# Shield.net
KiCad netlist of a schematic drawn in Altium Designer
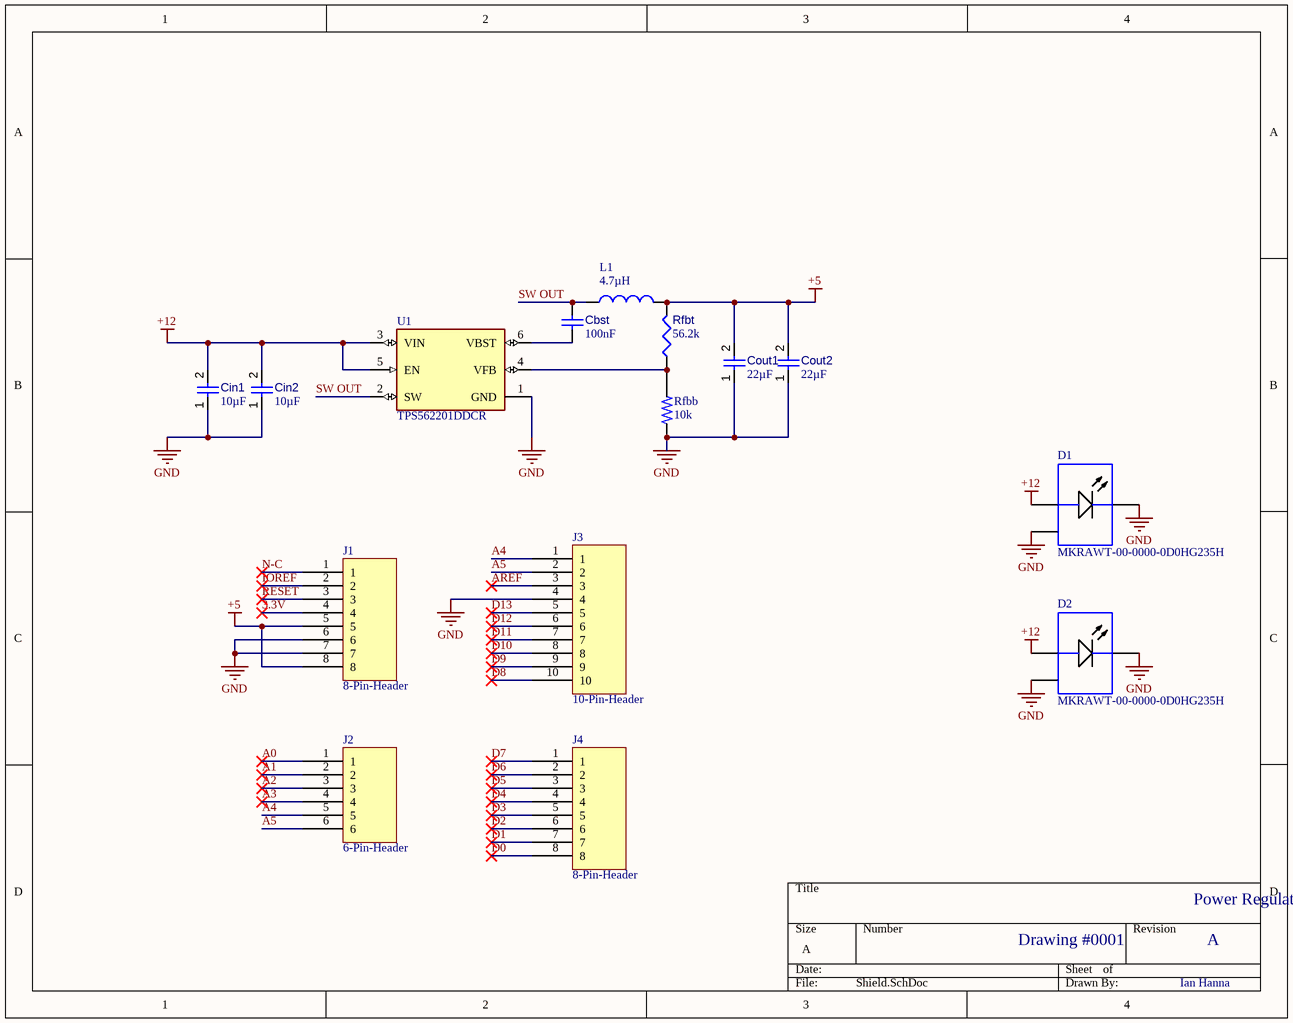
[diagram p0: Shield.SchDoc]

(export (version "E")
  (design (tool "Eeschema 10.0.6"))
  (components
    (comp (ref "Cbst")
      (value "100nF")
      (footprint "C0805")
      (description "0805 100 nF 25V ±10 % Tolerance X7R Surface Mount Multilayer Ceramic Capacitor")
      (fields (field (name "TOLERANCE") "10%") (field (name "Comment") "08053C104KAT2A"))
      (libsource (lib "") (part "CAP-NP-2_1"))
    )
    (comp (ref "Cin1")
      (value "10µF")
      (footprint "C0805")
      (fields (field (name "Comment") "MSAST219LB5106KTNA01"))
      (libsource (lib "Ian Hanna") (part "CAP-NP-2"))
    )
    (comp (ref "Cin2")
      (value "10µF")
      (footprint "C0805")
      (fields (field (name "Comment") "MSAST219LB5106KTNA01"))
      (libsource (lib "Ian Hanna") (part "CAP-NP-2"))
    )
    (comp (ref "Cout1")
      (value "22µF")
      (footprint "C0805")
      (fields (field (name "Comment") "MSASL219LB5226MTNA01"))
      (libsource (lib "Ian Hanna") (part "CAP-NP-2"))
    )
    (comp (ref "Cout2")
      (value "22µF")
      (footprint "C0805")
      (fields (field (name "Comment") "MSASL219LB5226MTNA01"))
      (libsource (lib "Ian Hanna") (part "CAP-NP-2"))
    )
    (comp (ref "D1")
      (value "MKRAWT-00-0000-0D0HG235H")
      (footprint "CREE-MK-R-2_V")
      (description "LED, White, 12 V, 2-Pin SMD, RoHS, Tape and Reel")
      (libsource (lib "Altium Content Vault") (part "LED_WHITE-3"))
    )
    (comp (ref "D2")
      (value "MKRAWT-00-0000-0D0HG235H")
      (footprint "CREE-MK-R-2_V")
      (description "LED, White, 12 V, 2-Pin SMD, RoHS, Tape and Reel")
      (libsource (lib "Altium Content Vault") (part "LED_WHITE-3"))
    )
    (comp (ref "J1")
      (value "8-Pin-Header")
      (footprint "8-Pin-Header-Footprint-1")
      (libsource (lib "Ian Hanna") (part "8-Pin-Header-Symbol-1"))
    )
    (comp (ref "J2")
      (value "6-Pin-Header")
      (footprint "6-Pin-Header-Footprint-1")
      (libsource (lib "Ian Hanna") (part "SSQ-106-03-T-S-Symbol-1"))
    )
    (comp (ref "J3")
      (value "10-Pin-Header")
      (footprint "10-Pin-Header-Footprint-1")
      (libsource (lib "Ian Hanna") (part "SSQ-110-03-T-S-Symbol-1"))
    )
    (comp (ref "J4")
      (value "8-Pin-Header")
      (footprint "8-Pin-Header-Footprint-1")
      (libsource (lib "Ian Hanna") (part "8-Pin-Header-Symbol-1"))
    )
    (comp (ref "L1")
      (value "4.7µH")
      (footprint "SRN6045")
      (description "Inductor Power Semi-Shielded Wirewound 4.7uH 30% 100KHz 15Q-Factor Ferrite 3A 37.6mOhm DCR T/R")
      (fields (field (name "TOLERANCE") "30%") (field (name "Comment") "SRN6045-4R7Y"))
      (libsource (lib "Ian Hanna") (part "IND-2"))
    )
    (comp (ref "Rfbb")
      (value "10k")
      (footprint "RESC0603X26N")
      (description "10 kOhms Â±1% 0.05W, 1/20W Chip Resistor 0201 (0603 Metric) Moisture Resistant Thick Film")
      (fields (field (name "MF") "Yageo") (field (name "MP") "RC0201FR-0710KL"))
      (libsource (lib "Ian Hanna") (part "RC0201FR-0710KL"))
    )
    (comp (ref "Rfbt")
      (value "56.2k")
      (footprint "RESC0603X26N")
      (description "Res Thick Film 0201 56.2K Ohm 1% 0.05W(1/20W) ±200ppm/C Molded SMD Paper T/R")
      (fields (field (name "TOLERANCE") "1%") (field (name "Comment") "RC0201FR-0756K2L"))
      (libsource (lib "Ian Hanna") (part "RES-2"))
    )
    (comp (ref "U1")
      (value "TPS562201DDCR")
      (footprint "FP-DDC0006A-IPC_C")
      (description "IC REG BUCK ADJ 2A TSOT23-6")
      (libsource (lib "Altium Content Vault") (part "957e164956730ea4bf6293280af19fc"))
    )
  )
  (nets
    (net (code "1") (name "+5") (class "Default")
      (node (ref "Cout1") (pin "2") (pinfunction "2_2") (pintype "passive"))
      (node (ref "Cout2") (pin "2") (pinfunction "2_2") (pintype "passive"))
      (node (ref "J1") (pin "5") (pinfunction "5_5") (pintype "passive"))
      (node (ref "J1") (pin "8") (pinfunction "8_8") (pintype "passive"))
      (node (ref "L1") (pin "2") (pinfunction "2_2") (pintype "passive"))
      (node (ref "Rfbt") (pin "2") (pinfunction "2_2") (pintype "passive"))
    )
    (net (code "2") (name "+12") (class "Default")
      (node (ref "Cin1") (pin "2") (pinfunction "2_2") (pintype "passive"))
      (node (ref "Cin2") (pin "2") (pinfunction "2_2") (pintype "passive"))
      (node (ref "D1") (pin "1") (pinfunction "A_1") (pintype "passive"))
      (node (ref "D2") (pin "1") (pinfunction "A_1") (pintype "passive"))
      (node (ref "U1") (pin "3") (pinfunction "VIN_3") (pintype "bidirectional"))
      (node (ref "U1") (pin "5") (pinfunction "EN_5") (pintype "input"))
    )
    (net (code "3") (name "/3.3V") (class "Default")
      (node (ref "J1") (pin "4") (pinfunction "4_4") (pintype "passive+no_connect"))
    )
    (net (code "4") (name "/A0") (class "Default")
      (node (ref "J2") (pin "1") (pinfunction "1_1") (pintype "passive+no_connect"))
    )
    (net (code "5") (name "/A1") (class "Default")
      (node (ref "J2") (pin "2") (pinfunction "2_2") (pintype "passive+no_connect"))
    )
    (net (code "6") (name "/A2") (class "Default")
      (node (ref "J2") (pin "3") (pinfunction "3_3") (pintype "passive+no_connect"))
    )
    (net (code "7") (name "/A3") (class "Default")
      (node (ref "J2") (pin "4") (pinfunction "4_4") (pintype "passive+no_connect"))
    )
    (net (code "8") (name "/A4") (class "Default")
      (node (ref "J2") (pin "5") (pinfunction "5_5") (pintype "passive"))
      (node (ref "J3") (pin "1") (pinfunction "1_1") (pintype "passive"))
    )
    (net (code "9") (name "/A5") (class "Default")
      (node (ref "J2") (pin "6") (pinfunction "6_6") (pintype "passive"))
      (node (ref "J3") (pin "2") (pinfunction "2_2") (pintype "passive"))
    )
    (net (code "10") (name "/AREF") (class "Default")
      (node (ref "J3") (pin "3") (pinfunction "3_3") (pintype "passive+no_connect"))
    )
    (net (code "11") (name "/D0") (class "Default")
      (node (ref "J4") (pin "8") (pinfunction "8_8") (pintype "passive+no_connect"))
    )
    (net (code "12") (name "/D1") (class "Default")
      (node (ref "J4") (pin "7") (pinfunction "7_7") (pintype "passive+no_connect"))
    )
    (net (code "13") (name "/D2") (class "Default")
      (node (ref "J4") (pin "6") (pinfunction "6_6") (pintype "passive+no_connect"))
    )
    (net (code "14") (name "/D3") (class "Default")
      (node (ref "J4") (pin "5") (pinfunction "5_5") (pintype "passive+no_connect"))
    )
    (net (code "15") (name "/D4") (class "Default")
      (node (ref "J4") (pin "4") (pinfunction "4_4") (pintype "passive+no_connect"))
    )
    (net (code "16") (name "/D5") (class "Default")
      (node (ref "J4") (pin "3") (pinfunction "3_3") (pintype "passive+no_connect"))
    )
    (net (code "17") (name "/D6") (class "Default")
      (node (ref "J4") (pin "2") (pinfunction "2_2") (pintype "passive+no_connect"))
    )
    (net (code "18") (name "/D7") (class "Default")
      (node (ref "J4") (pin "1") (pinfunction "1_1") (pintype "passive+no_connect"))
    )
    (net (code "19") (name "/D8") (class "Default")
      (node (ref "J3") (pin "10") (pinfunction "10_10") (pintype "passive+no_connect"))
    )
    (net (code "20") (name "/D9") (class "Default")
      (node (ref "J3") (pin "9") (pinfunction "9_9") (pintype "passive+no_connect"))
    )
    (net (code "21") (name "/D10") (class "Default")
      (node (ref "J3") (pin "8") (pinfunction "8_8") (pintype "passive+no_connect"))
    )
    (net (code "22") (name "/D11") (class "Default")
      (node (ref "J3") (pin "7") (pinfunction "7_7") (pintype "passive+no_connect"))
    )
    (net (code "23") (name "/D12") (class "Default")
      (node (ref "J3") (pin "6") (pinfunction "6_6") (pintype "passive+no_connect"))
    )
    (net (code "24") (name "/D13") (class "Default")
      (node (ref "J3") (pin "5") (pinfunction "5_5") (pintype "passive+no_connect"))
    )
    (net (code "25") (name "/IOREF") (class "Default")
      (node (ref "J1") (pin "2") (pinfunction "2_2") (pintype "passive+no_connect"))
    )
    (net (code "26") (name "/N-C") (class "Default")
      (node (ref "J1") (pin "1") (pinfunction "1_1") (pintype "passive+no_connect"))
    )
    (net (code "27") (name "/RESET") (class "Default")
      (node (ref "J1") (pin "3") (pinfunction "3_3") (pintype "passive+no_connect"))
    )
    (net (code "28") (name "/SW OUT") (class "Default")
      (node (ref "Cbst") (pin "1") (pinfunction "1_1") (pintype "passive"))
      (node (ref "L1") (pin "1") (pinfunction "1_1") (pintype "passive"))
      (node (ref "U1") (pin "2") (pinfunction "SW_2") (pintype "bidirectional"))
    )
    (net (code "29") (name "GND") (class "Default")
      (node (ref "Cin1") (pin "1") (pinfunction "1_1") (pintype "passive"))
      (node (ref "Cin2") (pin "1") (pinfunction "1_1") (pintype "passive"))
      (node (ref "Cout1") (pin "1") (pinfunction "1_1") (pintype "passive"))
      (node (ref "Cout2") (pin "1") (pinfunction "1_1") (pintype "passive"))
      (node (ref "D1") (pin "2") (pinfunction "K_2") (pintype "passive"))
      (node (ref "D1") (pin "3") (pinfunction "EP_3") (pintype "passive"))
      (node (ref "D2") (pin "2") (pinfunction "K_2") (pintype "passive"))
      (node (ref "D2") (pin "3") (pinfunction "EP_3") (pintype "passive"))
      (node (ref "J1") (pin "6") (pinfunction "6_6") (pintype "passive"))
      (node (ref "J1") (pin "7") (pinfunction "7_7") (pintype "passive"))
      (node (ref "J3") (pin "4") (pinfunction "4_4") (pintype "passive"))
      (node (ref "Rfbb") (pin "1") (pinfunction "1_1") (pintype "passive"))
      (node (ref "U1") (pin "1") (pinfunction "GND_1") (pintype "power_in"))
    )
    (net (code "30") (name "Net-(U1-VBST)") (class "Default")
      (node (ref "Cbst") (pin "2") (pinfunction "2_2") (pintype "passive"))
      (node (ref "U1") (pin "6") (pinfunction "VBST_6") (pintype "bidirectional"))
    )
    (net (code "31") (name "Net-(U1-VFB)") (class "Default")
      (node (ref "Rfbb") (pin "2") (pinfunction "2_2") (pintype "passive"))
      (node (ref "Rfbt") (pin "1") (pinfunction "1_1") (pintype "passive"))
      (node (ref "U1") (pin "4") (pinfunction "VFB_4") (pintype "bidirectional"))
    )
  )
)
